# InterfaceBoard.net
KiCad netlist of a schematic drawn in EAGLE
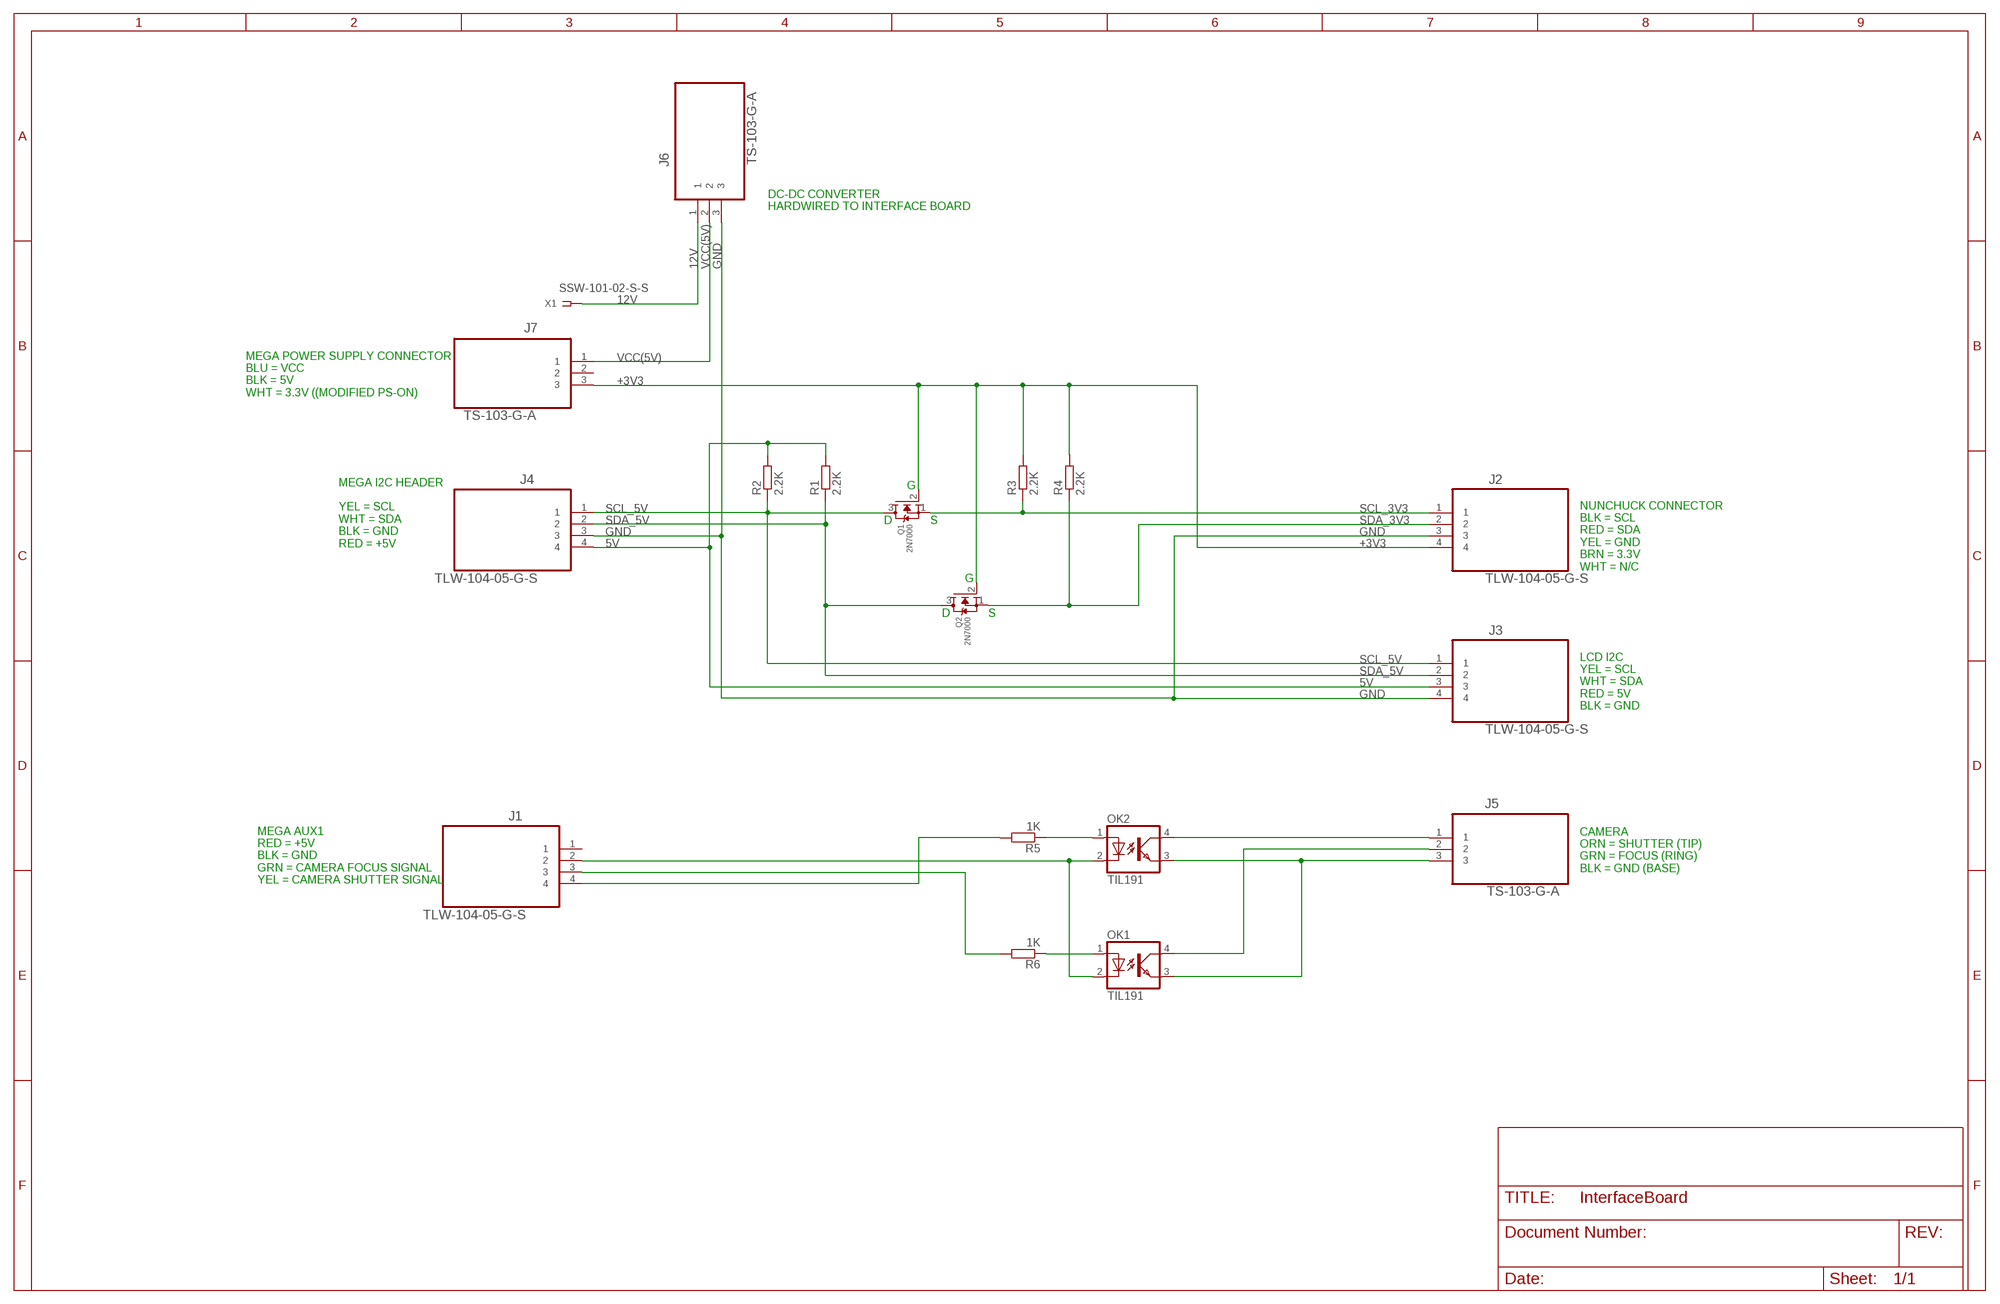
[diagram p0: schematic, sheet 1]

(export (version "E")
  (design (tool "Eeschema 10.0.6"))
  (components
    (comp (ref "J1")
      (value "TLW-104-05-G-S")
      (footprint "eagle-import:SAMTEC_TLW-104-05-G-S")
      (libsource (lib "eagle-import") (part "TLW-104-05-G-S"))
    )
    (comp (ref "J2")
      (value "TLW-104-05-G-S")
      (footprint "eagle-import:SAMTEC_TLW-104-05-G-S")
      (libsource (lib "eagle-import") (part "TLW-104-05-G-S"))
    )
    (comp (ref "J3")
      (value "TLW-104-05-G-S")
      (footprint "eagle-import:SAMTEC_TLW-104-05-G-S")
      (libsource (lib "eagle-import") (part "TLW-104-05-G-S"))
    )
    (comp (ref "J4")
      (value "TLW-104-05-G-S")
      (footprint "eagle-import:SAMTEC_TLW-104-05-G-S")
      (libsource (lib "eagle-import") (part "TLW-104-05-G-S"))
    )
    (comp (ref "J5")
      (value "TS-103-G-A")
      (footprint "eagle-import:SAMTEC_TS-103-G-A")
      (libsource (lib "eagle-import") (part "TS-103-G-A"))
    )
    (comp (ref "J6")
      (value "TS-103-G-A")
      (footprint "eagle-import:SAMTEC_TS-103-G-A")
      (libsource (lib "eagle-import") (part "TS-103-G-A"))
    )
    (comp (ref "J7")
      (value "TS-103-G-A")
      (footprint "eagle-import:SAMTEC_TS-103-G-A")
      (libsource (lib "eagle-import") (part "TS-103-G-A"))
    )
    (comp (ref "OK1")
      (value "TIL191")
      (footprint "eagle-import:DIL04")
      (libsource (lib "eagle-import") (part "TIL191"))
    )
    (comp (ref "OK2")
      (value "TIL191")
      (footprint "eagle-import:DIL04")
      (libsource (lib "eagle-import") (part "TIL191"))
    )
    (comp (ref "Q1")
      (value "2N7000")
      (footprint "eagle-import:SOT23")
      (libsource (lib "eagle-import") (part "MOSFET-NREFLOW"))
    )
    (comp (ref "Q2")
      (value "2N7000")
      (footprint "eagle-import:SOT23")
      (libsource (lib "eagle-import") (part "MOSFET-NREFLOW"))
    )
    (comp (ref "R1")
      (value "2.2K")
      (footprint "eagle-import:0207_12")
      (libsource (lib "eagle-import") (part "R-EU_0207/12"))
    )
    (comp (ref "R2")
      (value "2.2K")
      (footprint "eagle-import:0207_12")
      (libsource (lib "eagle-import") (part "R-EU_0207/12"))
    )
    (comp (ref "R3")
      (value "2.2K")
      (footprint "eagle-import:0207_12")
      (libsource (lib "eagle-import") (part "R-EU_0207/12"))
    )
    (comp (ref "R4")
      (value "2.2K")
      (footprint "eagle-import:0207_12")
      (libsource (lib "eagle-import") (part "R-EU_0207/12"))
    )
    (comp (ref "R5")
      (value "1K")
      (footprint "eagle-import:0207_12")
      (libsource (lib "eagle-import") (part "R-EU_0207/12"))
    )
    (comp (ref "R6")
      (value "1K")
      (footprint "eagle-import:0207_12")
      (libsource (lib "eagle-import") (part "R-EU_0207/12"))
    )
    (comp (ref "X1")
      (value "SSW-101-02-S-S")
      (footprint "eagle-import:SSW-101-02-S-S")
      (libsource (lib "eagle-import") (part "SSW-101-02-S-S"))
    )
  )
  (nets
    (net (code "1") (name "/+3V3") (class "Default")
      (node (ref "J2") (pin "4") (pinfunction "4_4") (pintype "passive"))
      (node (ref "J7") (pin "3") (pinfunction "3_3") (pintype "passive"))
      (node (ref "Q1") (pin "2") (pinfunction "G_2") (pintype "bidirectional"))
      (node (ref "Q2") (pin "2") (pinfunction "G_2") (pintype "bidirectional"))
      (node (ref "R3") (pin "2") (pinfunction "2_2") (pintype "passive"))
      (node (ref "R4") (pin "2") (pinfunction "2_2") (pintype "passive"))
    )
    (net (code "2") (name "/5V") (class "Default")
      (node (ref "J3") (pin "3") (pinfunction "3_3") (pintype "passive"))
      (node (ref "J4") (pin "4") (pinfunction "4_4") (pintype "passive"))
      (node (ref "R1") (pin "2") (pinfunction "2_2") (pintype "passive"))
      (node (ref "R2") (pin "2") (pinfunction "2_2") (pintype "passive"))
    )
    (net (code "3") (name "/12V") (class "Default")
      (node (ref "J6") (pin "1") (pinfunction "1_1") (pintype "passive"))
      (node (ref "X1") (pin "1") (pinfunction "1_1") (pintype "passive"))
    )
    (net (code "4") (name "/GND") (class "Default")
      (node (ref "J2") (pin "3") (pinfunction "3_3") (pintype "passive"))
      (node (ref "J3") (pin "4") (pinfunction "4_4") (pintype "passive"))
      (node (ref "J4") (pin "3") (pinfunction "3_3") (pintype "passive"))
      (node (ref "J6") (pin "3") (pinfunction "3_3") (pintype "passive"))
    )
    (net (code "5") (name "/SCL_3V3") (class "Default")
      (node (ref "J2") (pin "1") (pinfunction "1_1") (pintype "passive"))
      (node (ref "Q1") (pin "1") (pinfunction "S_1") (pintype "bidirectional"))
      (node (ref "R3") (pin "1") (pinfunction "1_1") (pintype "passive"))
    )
    (net (code "6") (name "/SCL_5V") (class "Default")
      (node (ref "J3") (pin "1") (pinfunction "1_1") (pintype "passive"))
      (node (ref "J4") (pin "1") (pinfunction "1_1") (pintype "passive"))
      (node (ref "Q1") (pin "3") (pinfunction "D_3") (pintype "bidirectional"))
      (node (ref "R2") (pin "1") (pinfunction "1_1") (pintype "passive"))
    )
    (net (code "7") (name "/SDA_3V3") (class "Default")
      (node (ref "J2") (pin "2") (pinfunction "2_2") (pintype "passive"))
      (node (ref "Q2") (pin "1") (pinfunction "S_1") (pintype "bidirectional"))
      (node (ref "R4") (pin "1") (pinfunction "1_1") (pintype "passive"))
    )
    (net (code "8") (name "/SDA_5V") (class "Default")
      (node (ref "J3") (pin "2") (pinfunction "2_2") (pintype "passive"))
      (node (ref "J4") (pin "2") (pinfunction "2_2") (pintype "passive"))
      (node (ref "Q2") (pin "3") (pinfunction "D_3") (pintype "bidirectional"))
      (node (ref "R1") (pin "1") (pinfunction "1_1") (pintype "passive"))
    )
    (net (code "9") (name "/VCC(5V)") (class "Default")
      (node (ref "J6") (pin "2") (pinfunction "2_2") (pintype "passive"))
      (node (ref "J7") (pin "1") (pinfunction "1_1") (pintype "passive"))
    )
    (net (code "10") (name "Net-(J1-Pad3)") (class "Default")
      (node (ref "J1") (pin "3") (pinfunction "3_3") (pintype "passive"))
      (node (ref "R6") (pin "2") (pinfunction "2_2") (pintype "passive"))
    )
    (net (code "11") (name "Net-(J1-Pad4)") (class "Default")
      (node (ref "J1") (pin "4") (pinfunction "4_4") (pintype "passive"))
      (node (ref "R5") (pin "2") (pinfunction "2_2") (pintype "passive"))
    )
    (net (code "12") (name "Net-(OK1-A)") (class "Default")
      (node (ref "OK1") (pin "1") (pinfunction "A_1") (pintype "passive"))
      (node (ref "R6") (pin "1") (pinfunction "1_1") (pintype "passive"))
    )
    (net (code "13") (name "Net-(OK1-C)") (class "Default")
      (node (ref "J1") (pin "2") (pinfunction "2_2") (pintype "passive"))
      (node (ref "OK1") (pin "2") (pinfunction "C_2") (pintype "passive"))
      (node (ref "OK2") (pin "2") (pinfunction "C_2") (pintype "passive"))
    )
    (net (code "14") (name "Net-(OK1-COL)") (class "Default")
      (node (ref "J5") (pin "2") (pinfunction "2_2") (pintype "passive"))
      (node (ref "OK1") (pin "4") (pinfunction "COL_4") (pintype "passive"))
    )
    (net (code "15") (name "Net-(OK1-EMIT)") (class "Default")
      (node (ref "J5") (pin "3") (pinfunction "3_3") (pintype "passive"))
      (node (ref "OK1") (pin "3") (pinfunction "EMIT_3") (pintype "passive"))
      (node (ref "OK2") (pin "3") (pinfunction "EMIT_3") (pintype "passive"))
    )
    (net (code "16") (name "Net-(OK2-A)") (class "Default")
      (node (ref "OK2") (pin "1") (pinfunction "A_1") (pintype "passive"))
      (node (ref "R5") (pin "1") (pinfunction "1_1") (pintype "passive"))
    )
    (net (code "17") (name "Net-(OK2-COL)") (class "Default")
      (node (ref "J5") (pin "1") (pinfunction "1_1") (pintype "passive"))
      (node (ref "OK2") (pin "4") (pinfunction "COL_4") (pintype "passive"))
    )
    (net (code "18") (name "unconnected-(J1-Pad1)") (class "Default")
      (node (ref "J1") (pin "1") (pinfunction "1_1") (pintype "passive"))
    )
    (net (code "19") (name "unconnected-(J7-Pad2)") (class "Default")
      (node (ref "J7") (pin "2") (pinfunction "2_2") (pintype "passive"))
    )
  )
)
